# test-board-64.net
KiCad netlist of a schematic drawn in EAGLE
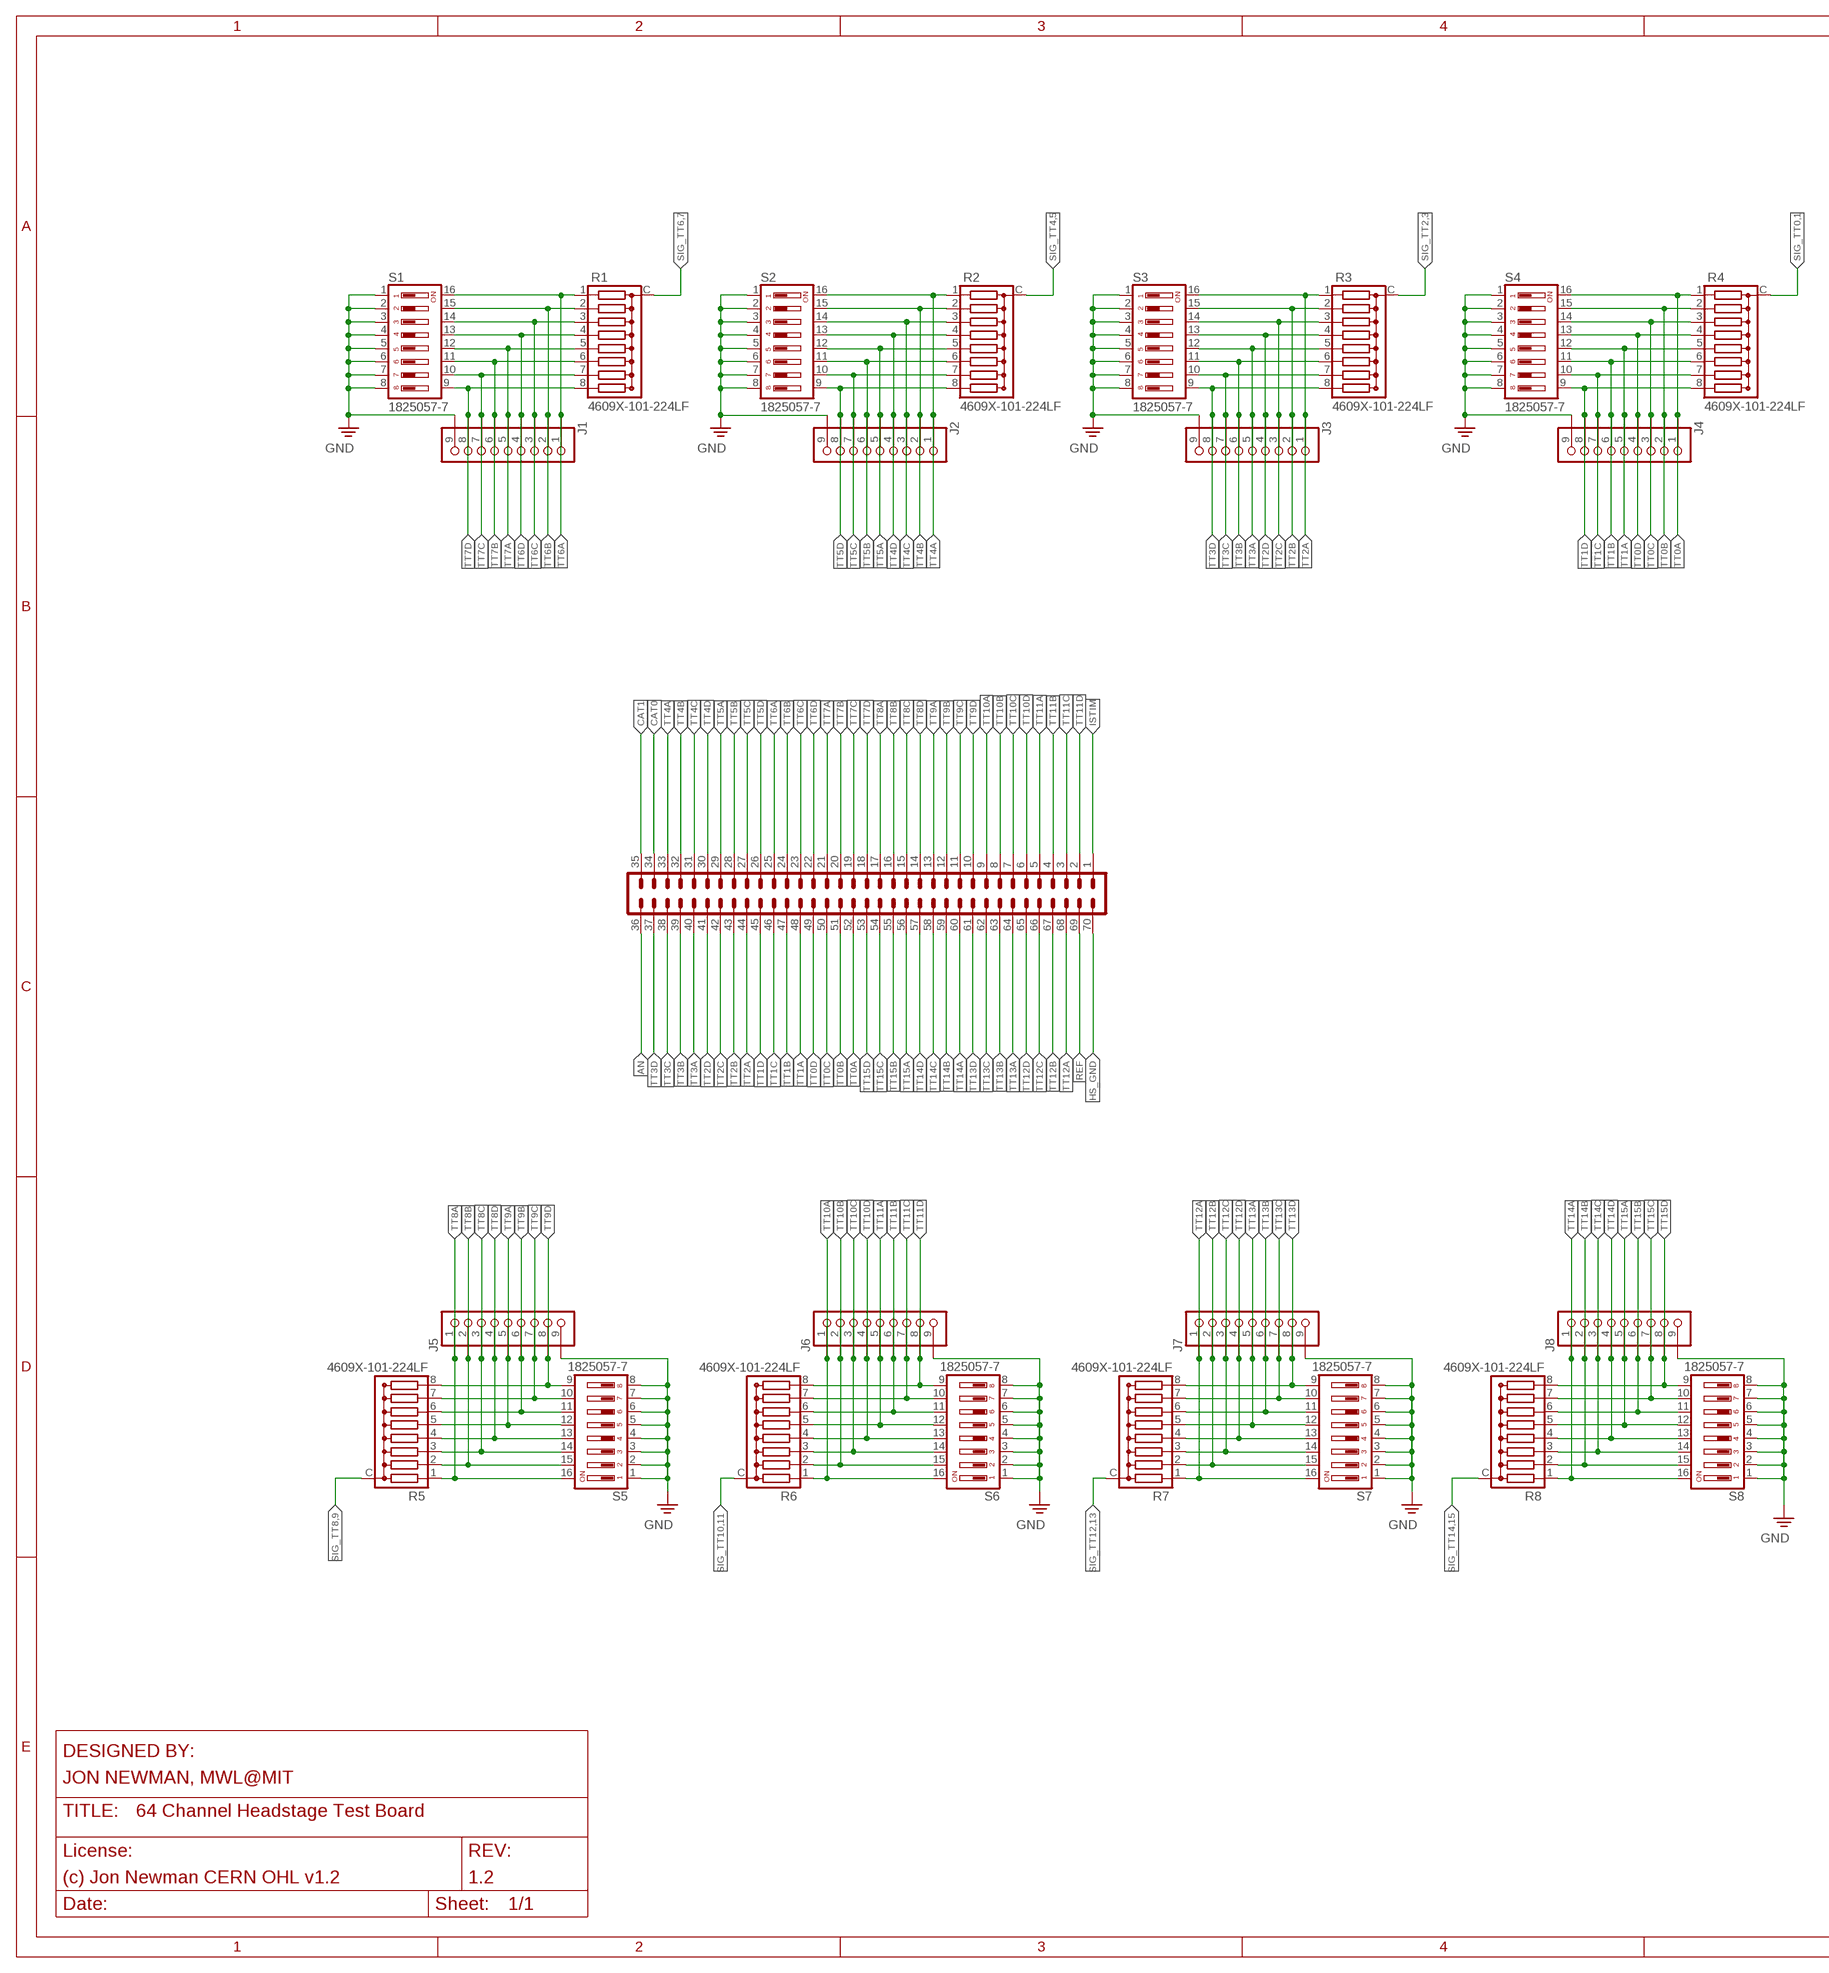
[diagram p0: schematic, sheet 1, part 1 of 2]
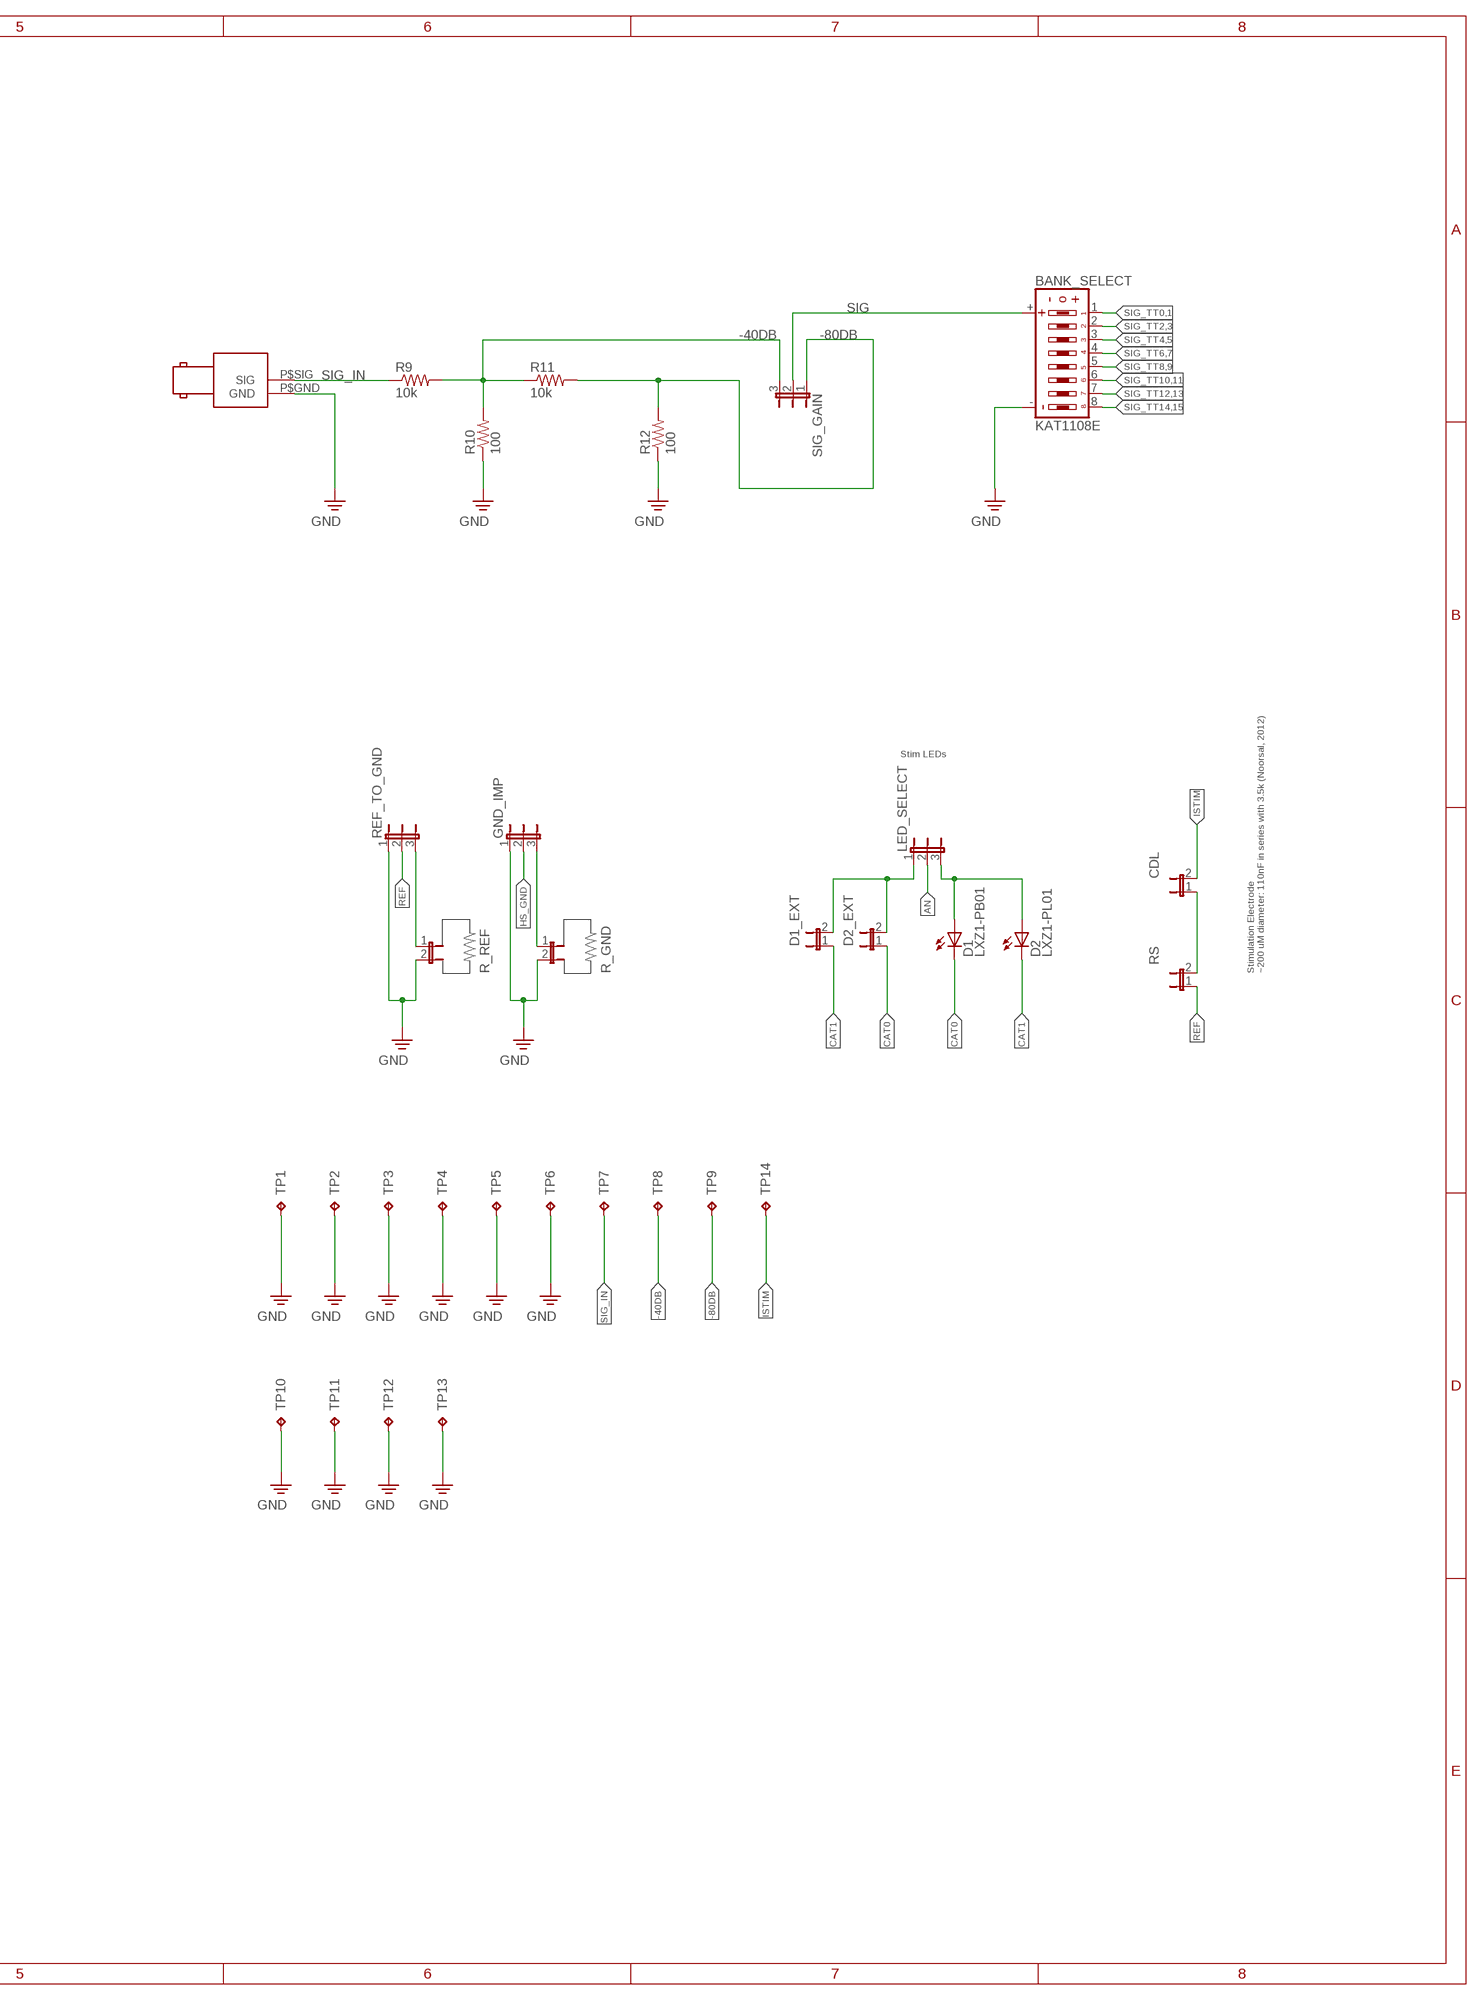
[diagram p1: schematic, sheet 1, part 2 of 2]

(export (version "E")
  (design (tool "Eeschema 10.0.6"))
  (components
    (comp (ref "BANK_SELECT")
      (value "KAT1108E")
      (footprint "eagle-import:206-124_DIP8-SPDT")
      (libsource (lib "eagle-import") (part "DIPSW-008-SPDT_206-124"))
    )
    (comp (ref "CDL")
      (value "SOC2-0.1\"")
      (footprint "eagle-import:JP2")
      (libsource (lib "eagle-import") (part "JP2E_THRU-HOLE"))
    )
    (comp (ref "D1")
      (value "LXZ1-PB01")
      (footprint "eagle-import:LXZ1")
      (libsource (lib "eagle-import") (part "LED_LXZ1"))
    )
    (comp (ref "D1_EXT")
      (value "SOC2-0.1\"")
      (footprint "eagle-import:JP2")
      (libsource (lib "eagle-import") (part "JP2E_THRU-HOLE"))
    )
    (comp (ref "D2")
      (value "LXZ1-PL01")
      (footprint "eagle-import:LXZ1")
      (libsource (lib "eagle-import") (part "LED_LXZ1"))
    )
    (comp (ref "D2_EXT")
      (value "SOC2-0.1\"")
      (footprint "eagle-import:JP2")
      (libsource (lib "eagle-import") (part "JP2E_THRU-HOLE"))
    )
    (comp (ref "GND_IMP")
      (value "JP3-0.1\"")
      (footprint "eagle-import:JP3")
      (libsource (lib "eagle-import") (part "JP3E"))
    )
    (comp (ref "HEADSTAGE")
      (value "DF40C-70DP-0.4V(51)")
      (footprint "eagle-import:DDF40-70REC-LRG")
      (libsource (lib "eagle-import") (part "PINHD-2X35_DF40REF-LRG"))
    )
    (comp (ref "J1")
      (value "PINHD-1X9")
      (footprint "eagle-import:1X09")
      (libsource (lib "eagle-import") (part "PINHD-1X9"))
    )
    (comp (ref "J2")
      (value "PINHD-1X9")
      (footprint "eagle-import:1X09")
      (libsource (lib "eagle-import") (part "PINHD-1X9"))
    )
    (comp (ref "J3")
      (value "PINHD-1X9")
      (footprint "eagle-import:1X09")
      (libsource (lib "eagle-import") (part "PINHD-1X9"))
    )
    (comp (ref "J4")
      (value "PINHD-1X9")
      (footprint "eagle-import:1X09")
      (libsource (lib "eagle-import") (part "PINHD-1X9"))
    )
    (comp (ref "J5")
      (value "PINHD-1X9")
      (footprint "eagle-import:1X09")
      (libsource (lib "eagle-import") (part "PINHD-1X9"))
    )
    (comp (ref "J6")
      (value "PINHD-1X9")
      (footprint "eagle-import:1X09")
      (libsource (lib "eagle-import") (part "PINHD-1X9"))
    )
    (comp (ref "J7")
      (value "PINHD-1X9")
      (footprint "eagle-import:1X09")
      (libsource (lib "eagle-import") (part "PINHD-1X9"))
    )
    (comp (ref "J8")
      (value "PINHD-1X9")
      (footprint "eagle-import:1X09")
      (libsource (lib "eagle-import") (part "PINHD-1X9"))
    )
    (comp (ref "LED_SELECT")
      (value "JP3-0.1\"")
      (footprint "eagle-import:JP3")
      (libsource (lib "eagle-import") (part "JP3E"))
    )
    (comp (ref "R1")
      (value "4609X-101-224LF")
      (footprint "eagle-import:RNX8-0.1")
      (libsource (lib "eagle-import") (part "RN1X8"))
    )
    (comp (ref "R2")
      (value "4609X-101-224LF")
      (footprint "eagle-import:RNX8-0.1")
      (libsource (lib "eagle-import") (part "RN1X8"))
    )
    (comp (ref "R3")
      (value "4609X-101-224LF")
      (footprint "eagle-import:RNX8-0.1")
      (libsource (lib "eagle-import") (part "RN1X8"))
    )
    (comp (ref "R4")
      (value "4609X-101-224LF")
      (footprint "eagle-import:RNX8-0.1")
      (libsource (lib "eagle-import") (part "RN1X8"))
    )
    (comp (ref "R5")
      (value "4609X-101-224LF")
      (footprint "eagle-import:RNX8-0.1")
      (libsource (lib "eagle-import") (part "RN1X8"))
    )
    (comp (ref "R6")
      (value "4609X-101-224LF")
      (footprint "eagle-import:RNX8-0.1")
      (libsource (lib "eagle-import") (part "RN1X8"))
    )
    (comp (ref "R7")
      (value "4609X-101-224LF")
      (footprint "eagle-import:RNX8-0.1")
      (libsource (lib "eagle-import") (part "RN1X8"))
    )
    (comp (ref "R8")
      (value "4609X-101-224LF")
      (footprint "eagle-import:RNX8-0.1")
      (libsource (lib "eagle-import") (part "RN1X8"))
    )
    (comp (ref "R9")
      (value "10k")
      (footprint "eagle-import:0805")
      (libsource (lib "eagle-import") (part "R_0805"))
    )
    (comp (ref "R10")
      (value "100")
      (footprint "eagle-import:0805")
      (libsource (lib "eagle-import") (part "R_0805"))
    )
    (comp (ref "R11")
      (value "10k")
      (footprint "eagle-import:0805")
      (libsource (lib "eagle-import") (part "R_0805"))
    )
    (comp (ref "R12")
      (value "100")
      (footprint "eagle-import:0805")
      (libsource (lib "eagle-import") (part "R_0805"))
    )
    (comp (ref "REF_TO_GND")
      (value "JP3-0.1\"")
      (footprint "eagle-import:JP3")
      (libsource (lib "eagle-import") (part "JP3E"))
    )
    (comp (ref "RS")
      (value "SOC2-0.1\"")
      (footprint "eagle-import:JP2")
      (libsource (lib "eagle-import") (part "JP2E_THRU-HOLE"))
    )
    (comp (ref "R_GND")
      (value "SOC2-0.1\"")
      (footprint "eagle-import:JP2")
      (libsource (lib "eagle-import") (part "JP2E_THRU-HOLE"))
    )
    (comp (ref "R_REF")
      (value "SOC2-0.1\"")
      (footprint "eagle-import:JP2")
      (libsource (lib "eagle-import") (part "JP2E_THRU-HOLE"))
    )
    (comp (ref "S1")
      (value "1825057-7")
      (footprint "eagle-import:ADE_DIP8-SPST")
      (libsource (lib "eagle-import") (part "DIPSW-008_ADE"))
    )
    (comp (ref "S2")
      (value "1825057-7")
      (footprint "eagle-import:ADE_DIP8-SPST")
      (libsource (lib "eagle-import") (part "DIPSW-008_ADE"))
    )
    (comp (ref "S3")
      (value "1825057-7")
      (footprint "eagle-import:ADE_DIP8-SPST")
      (libsource (lib "eagle-import") (part "DIPSW-008_ADE"))
    )
    (comp (ref "S4")
      (value "1825057-7")
      (footprint "eagle-import:ADE_DIP8-SPST")
      (libsource (lib "eagle-import") (part "DIPSW-008_ADE"))
    )
    (comp (ref "S5")
      (value "1825057-7")
      (footprint "eagle-import:ADE_DIP8-SPST")
      (libsource (lib "eagle-import") (part "DIPSW-008_ADE"))
    )
    (comp (ref "S6")
      (value "1825057-7")
      (footprint "eagle-import:ADE_DIP8-SPST")
      (libsource (lib "eagle-import") (part "DIPSW-008_ADE"))
    )
    (comp (ref "S7")
      (value "1825057-7")
      (footprint "eagle-import:ADE_DIP8-SPST")
      (libsource (lib "eagle-import") (part "DIPSW-008_ADE"))
    )
    (comp (ref "S8")
      (value "1825057-7")
      (footprint "eagle-import:ADE_DIP8-SPST")
      (libsource (lib "eagle-import") (part "DIPSW-008_ADE"))
    )
    (comp (ref "SIG_GAIN")
      (value "JP3-0.1\"")
      (footprint "eagle-import:JP3")
      (libsource (lib "eagle-import") (part "JP3E"))
    )
    (comp (ref "SIG_IN")
      (value "1-1634622-0")
      (footprint "eagle-import:BNC_RIGHT_ANGLE")
      (libsource (lib "eagle-import") (part "BNC_RIGHT_ANGLE"))
    )
    (comp (ref "TP1")
      (value "GND")
      (footprint "eagle-import:P1-20")
      (libsource (lib "eagle-import") (part "TPPAD1-20"))
    )
    (comp (ref "TP2")
      (value "GND")
      (footprint "eagle-import:P1-20")
      (libsource (lib "eagle-import") (part "TPPAD1-20"))
    )
    (comp (ref "TP3")
      (value "GND")
      (footprint "eagle-import:P1-20")
      (libsource (lib "eagle-import") (part "TPPAD1-20"))
    )
    (comp (ref "TP4")
      (value "GND")
      (footprint "eagle-import:P1-20")
      (libsource (lib "eagle-import") (part "TPPAD1-20"))
    )
    (comp (ref "TP5")
      (value "GND")
      (footprint "eagle-import:P1-20")
      (libsource (lib "eagle-import") (part "TPPAD1-20"))
    )
    (comp (ref "TP6")
      (value "GND")
      (footprint "eagle-import:P1-20")
      (libsource (lib "eagle-import") (part "TPPAD1-20"))
    )
    (comp (ref "TP7")
      (value "SIG_IN")
      (footprint "eagle-import:P1-20")
      (libsource (lib "eagle-import") (part "TPPAD1-20"))
    )
    (comp (ref "TP8")
      (value "-40dB")
      (footprint "eagle-import:P1-20")
      (libsource (lib "eagle-import") (part "TPPAD1-20"))
    )
    (comp (ref "TP9")
      (value "-80dB")
      (footprint "eagle-import:P1-20")
      (libsource (lib "eagle-import") (part "TPPAD1-20"))
    )
    (comp (ref "TP10")
      (value "TP_4-40")
      (footprint "eagle-import:4-40_PLATED")
      (libsource (lib "eagle-import") (part "TP_4-40"))
    )
    (comp (ref "TP11")
      (value "TP_4-40")
      (footprint "eagle-import:4-40_PLATED")
      (libsource (lib "eagle-import") (part "TP_4-40"))
    )
    (comp (ref "TP12")
      (value "TP_4-40")
      (footprint "eagle-import:4-40_PLATED")
      (libsource (lib "eagle-import") (part "TP_4-40"))
    )
    (comp (ref "TP13")
      (value "TP_4-40")
      (footprint "eagle-import:4-40_PLATED")
      (libsource (lib "eagle-import") (part "TP_4-40"))
    )
    (comp (ref "TP14")
      (value "V_ESTIM")
      (footprint "eagle-import:P1-20")
      (libsource (lib "eagle-import") (part "TPPAD1-20"))
    )
  )
  (nets
    (net (code "1") (name "-40DB") (class "Default")
      (node (ref "R10") (pin "2") (pinfunction "2_2") (pintype "passive"))
      (node (ref "R11") (pin "1") (pinfunction "1_1") (pintype "passive"))
      (node (ref "R9") (pin "2") (pinfunction "2_2") (pintype "passive"))
      (node (ref "SIG_GAIN") (pin "3") (pinfunction "3_3") (pintype "passive"))
      (node (ref "TP8") (pin "TP") (pinfunction "TP_TP") (pintype "input"))
    )
    (net (code "2") (name "-80DB") (class "Default")
      (node (ref "R11") (pin "2") (pinfunction "2_2") (pintype "passive"))
      (node (ref "R12") (pin "2") (pinfunction "2_2") (pintype "passive"))
      (node (ref "SIG_GAIN") (pin "1") (pinfunction "1_1") (pintype "passive"))
      (node (ref "TP9") (pin "TP") (pinfunction "TP_TP") (pintype "input"))
    )
    (net (code "3") (name "/SIG") (class "Default")
      (node (ref "BANK_SELECT") (pin "+") (pinfunction "+_+") (pintype "passive"))
      (node (ref "SIG_GAIN") (pin "2") (pinfunction "2_2") (pintype "passive"))
    )
    (net (code "4") (name "AN") (class "Default")
      (node (ref "HEADSTAGE") (pin "36") (pinfunction "36_36") (pintype "bidirectional"))
      (node (ref "LED_SELECT") (pin "2") (pinfunction "2_2") (pintype "passive"))
    )
    (net (code "5") (name "CAT0") (class "Default")
      (node (ref "D1") (pin "C") (pinfunction "C_C") (pintype "passive"))
      (node (ref "D2_EXT") (pin "1") (pinfunction "1_1") (pintype "passive"))
      (node (ref "HEADSTAGE") (pin "34") (pinfunction "34_34") (pintype "bidirectional"))
    )
    (net (code "6") (name "CAT1") (class "Default")
      (node (ref "D1_EXT") (pin "1") (pinfunction "1_1") (pintype "passive"))
      (node (ref "D2") (pin "C") (pinfunction "C_C") (pintype "passive"))
      (node (ref "HEADSTAGE") (pin "35") (pinfunction "35_35") (pintype "bidirectional"))
    )
    (net (code "7") (name "GND") (class "Default")
      (node (ref "BANK_SELECT") (pin "-") (pinfunction "-_-") (pintype "passive"))
      (node (ref "GND_IMP") (pin "1") (pinfunction "1_1") (pintype "passive"))
      (node (ref "J1") (pin "9") (pinfunction "9_9") (pintype "passive"))
      (node (ref "J2") (pin "9") (pinfunction "9_9") (pintype "passive"))
      (node (ref "J3") (pin "9") (pinfunction "9_9") (pintype "passive"))
      (node (ref "J4") (pin "9") (pinfunction "9_9") (pintype "passive"))
      (node (ref "J5") (pin "9") (pinfunction "9_9") (pintype "passive"))
      (node (ref "J6") (pin "9") (pinfunction "9_9") (pintype "passive"))
      (node (ref "J7") (pin "9") (pinfunction "9_9") (pintype "passive"))
      (node (ref "J8") (pin "9") (pinfunction "9_9") (pintype "passive"))
      (node (ref "R10") (pin "1") (pinfunction "1_1") (pintype "passive"))
      (node (ref "R12") (pin "1") (pinfunction "1_1") (pintype "passive"))
      (node (ref "REF_TO_GND") (pin "1") (pinfunction "1_1") (pintype "passive"))
      (node (ref "R_GND") (pin "2") (pinfunction "2_2") (pintype "passive"))
      (node (ref "R_REF") (pin "2") (pinfunction "2_2") (pintype "passive"))
      (node (ref "S1") (pin "1") (pinfunction "1_1") (pintype "passive"))
      (node (ref "S1") (pin "2") (pinfunction "2_2") (pintype "passive"))
      (node (ref "S1") (pin "3") (pinfunction "3_3") (pintype "passive"))
      (node (ref "S1") (pin "4") (pinfunction "4_4") (pintype "passive"))
      (node (ref "S1") (pin "5") (pinfunction "5_5") (pintype "passive"))
      (node (ref "S1") (pin "6") (pinfunction "6_6") (pintype "passive"))
      (node (ref "S1") (pin "7") (pinfunction "7_7") (pintype "passive"))
      (node (ref "S1") (pin "8") (pinfunction "8_8") (pintype "passive"))
      (node (ref "S2") (pin "1") (pinfunction "1_1") (pintype "passive"))
      (node (ref "S2") (pin "2") (pinfunction "2_2") (pintype "passive"))
      (node (ref "S2") (pin "3") (pinfunction "3_3") (pintype "passive"))
      (node (ref "S2") (pin "4") (pinfunction "4_4") (pintype "passive"))
      (node (ref "S2") (pin "5") (pinfunction "5_5") (pintype "passive"))
      (node (ref "S2") (pin "6") (pinfunction "6_6") (pintype "passive"))
      (node (ref "S2") (pin "7") (pinfunction "7_7") (pintype "passive"))
      (node (ref "S2") (pin "8") (pinfunction "8_8") (pintype "passive"))
      (node (ref "S3") (pin "1") (pinfunction "1_1") (pintype "passive"))
      (node (ref "S3") (pin "2") (pinfunction "2_2") (pintype "passive"))
      (node (ref "S3") (pin "3") (pinfunction "3_3") (pintype "passive"))
      (node (ref "S3") (pin "4") (pinfunction "4_4") (pintype "passive"))
      (node (ref "S3") (pin "5") (pinfunction "5_5") (pintype "passive"))
      (node (ref "S3") (pin "6") (pinfunction "6_6") (pintype "passive"))
      (node (ref "S3") (pin "7") (pinfunction "7_7") (pintype "passive"))
      (node (ref "S3") (pin "8") (pinfunction "8_8") (pintype "passive"))
      (node (ref "S4") (pin "1") (pinfunction "1_1") (pintype "passive"))
      (node (ref "S4") (pin "2") (pinfunction "2_2") (pintype "passive"))
      (node (ref "S4") (pin "3") (pinfunction "3_3") (pintype "passive"))
      (node (ref "S4") (pin "4") (pinfunction "4_4") (pintype "passive"))
      (node (ref "S4") (pin "5") (pinfunction "5_5") (pintype "passive"))
      (node (ref "S4") (pin "6") (pinfunction "6_6") (pintype "passive"))
      (node (ref "S4") (pin "7") (pinfunction "7_7") (pintype "passive"))
      (node (ref "S4") (pin "8") (pinfunction "8_8") (pintype "passive"))
      (node (ref "S5") (pin "1") (pinfunction "1_1") (pintype "passive"))
      (node (ref "S5") (pin "2") (pinfunction "2_2") (pintype "passive"))
      (node (ref "S5") (pin "3") (pinfunction "3_3") (pintype "passive"))
      (node (ref "S5") (pin "4") (pinfunction "4_4") (pintype "passive"))
      (node (ref "S5") (pin "5") (pinfunction "5_5") (pintype "passive"))
      (node (ref "S5") (pin "6") (pinfunction "6_6") (pintype "passive"))
      (node (ref "S5") (pin "7") (pinfunction "7_7") (pintype "passive"))
      (node (ref "S5") (pin "8") (pinfunction "8_8") (pintype "passive"))
      (node (ref "S6") (pin "1") (pinfunction "1_1") (pintype "passive"))
      (node (ref "S6") (pin "2") (pinfunction "2_2") (pintype "passive"))
      (node (ref "S6") (pin "3") (pinfunction "3_3") (pintype "passive"))
      (node (ref "S6") (pin "4") (pinfunction "4_4") (pintype "passive"))
      (node (ref "S6") (pin "5") (pinfunction "5_5") (pintype "passive"))
      (node (ref "S6") (pin "6") (pinfunction "6_6") (pintype "passive"))
      (node (ref "S6") (pin "7") (pinfunction "7_7") (pintype "passive"))
      (node (ref "S6") (pin "8") (pinfunction "8_8") (pintype "passive"))
      (node (ref "S7") (pin "1") (pinfunction "1_1") (pintype "passive"))
      (node (ref "S7") (pin "2") (pinfunction "2_2") (pintype "passive"))
      (node (ref "S7") (pin "3") (pinfunction "3_3") (pintype "passive"))
      (node (ref "S7") (pin "4") (pinfunction "4_4") (pintype "passive"))
      (node (ref "S7") (pin "5") (pinfunction "5_5") (pintype "passive"))
      (node (ref "S7") (pin "6") (pinfunction "6_6") (pintype "passive"))
      (node (ref "S7") (pin "7") (pinfunction "7_7") (pintype "passive"))
      (node (ref "S7") (pin "8") (pinfunction "8_8") (pintype "passive"))
      (node (ref "S8") (pin "1") (pinfunction "1_1") (pintype "passive"))
      (node (ref "S8") (pin "2") (pinfunction "2_2") (pintype "passive"))
      (node (ref "S8") (pin "3") (pinfunction "3_3") (pintype "passive"))
      (node (ref "S8") (pin "4") (pinfunction "4_4") (pintype "passive"))
      (node (ref "S8") (pin "5") (pinfunction "5_5") (pintype "passive"))
      (node (ref "S8") (pin "6") (pinfunction "6_6") (pintype "passive"))
      (node (ref "S8") (pin "7") (pinfunction "7_7") (pintype "passive"))
      (node (ref "S8") (pin "8") (pinfunction "8_8") (pintype "passive"))
      (node (ref "SIG_IN") (pin "P$GND") (pinfunction "GND_P$GND") (pintype "bidirectional"))
      (node (ref "TP1") (pin "TP") (pinfunction "TP_TP") (pintype "input"))
      (node (ref "TP10") (pin "P$1") (pinfunction "TP_P$1") (pintype "input"))
      (node (ref "TP11") (pin "P$1") (pinfunction "TP_P$1") (pintype "input"))
      (node (ref "TP12") (pin "P$1") (pinfunction "TP_P$1") (pintype "input"))
      (node (ref "TP13") (pin "P$1") (pinfunction "TP_P$1") (pintype "input"))
      (node (ref "TP2") (pin "TP") (pinfunction "TP_TP") (pintype "input"))
      (node (ref "TP3") (pin "TP") (pinfunction "TP_TP") (pintype "input"))
      (node (ref "TP4") (pin "TP") (pinfunction "TP_TP") (pintype "input"))
      (node (ref "TP5") (pin "TP") (pinfunction "TP_TP") (pintype "input"))
      (node (ref "TP6") (pin "TP") (pinfunction "TP_TP") (pintype "input"))
    )
    (net (code "8") (name "HS_GND") (class "Default")
      (node (ref "GND_IMP") (pin "2") (pinfunction "2_2") (pintype "passive"))
      (node (ref "HEADSTAGE") (pin "70") (pinfunction "70_70") (pintype "bidirectional"))
    )
    (net (code "9") (name "ISTIM") (class "Default")
      (node (ref "CDL") (pin "2") (pinfunction "2_2") (pintype "passive"))
      (node (ref "HEADSTAGE") (pin "1") (pinfunction "1_1") (pintype "bidirectional"))
      (node (ref "TP14") (pin "TP") (pinfunction "TP_TP") (pintype "input"))
    )
    (net (code "10") (name "Net-(CDL-Pad1)") (class "Default")
      (node (ref "CDL") (pin "1") (pinfunction "1_1") (pintype "passive"))
      (node (ref "RS") (pin "2") (pinfunction "2_2") (pintype "passive"))
    )
    (net (code "11") (name "Net-(D1-PadA)") (class "Default")
      (node (ref "D1") (pin "A") (pinfunction "A_A") (pintype "passive"))
      (node (ref "D2") (pin "A") (pinfunction "A_A") (pintype "passive"))
      (node (ref "LED_SELECT") (pin "3") (pinfunction "3_3") (pintype "passive"))
    )
    (net (code "12") (name "Net-(D1_EXT-Pad2)") (class "Default")
      (node (ref "D1_EXT") (pin "2") (pinfunction "2_2") (pintype "passive"))
      (node (ref "D2_EXT") (pin "2") (pinfunction "2_2") (pintype "passive"))
      (node (ref "LED_SELECT") (pin "1") (pinfunction "1_1") (pintype "passive"))
    )
    (net (code "13") (name "Net-(GND_IMP-Pad3)") (class "Default")
      (node (ref "GND_IMP") (pin "3") (pinfunction "3_3") (pintype "passive"))
      (node (ref "R_GND") (pin "1") (pinfunction "1_1") (pintype "passive"))
    )
    (net (code "14") (name "Net-(REF_TO_GND-Pad3)") (class "Default")
      (node (ref "REF_TO_GND") (pin "3") (pinfunction "3_3") (pintype "passive"))
      (node (ref "R_REF") (pin "1") (pinfunction "1_1") (pintype "passive"))
    )
    (net (code "15") (name "REF") (class "Default")
      (node (ref "HEADSTAGE") (pin "69") (pinfunction "69_69") (pintype "bidirectional"))
      (node (ref "REF_TO_GND") (pin "2") (pinfunction "2_2") (pintype "passive"))
      (node (ref "RS") (pin "1") (pinfunction "1_1") (pintype "passive"))
    )
    (net (code "16") (name "SIG_IN") (class "Default")
      (node (ref "R9") (pin "1") (pinfunction "1_1") (pintype "passive"))
      (node (ref "SIG_IN") (pin "P$SIG") (pinfunction "SIG_P$SIG") (pintype "bidirectional"))
      (node (ref "TP7") (pin "TP") (pinfunction "TP_TP") (pintype "input"))
    )
    (net (code "17") (name "SIG_TT0,1") (class "Default")
      (node (ref "BANK_SELECT") (pin "1") (pinfunction "1_1") (pintype "passive"))
      (node (ref "R4") (pin "C") (pinfunction "C_C") (pintype "passive"))
    )
    (net (code "18") (name "SIG_TT2,3") (class "Default")
      (node (ref "BANK_SELECT") (pin "2") (pinfunction "2_2") (pintype "passive"))
      (node (ref "R3") (pin "C") (pinfunction "C_C") (pintype "passive"))
    )
    (net (code "19") (name "SIG_TT4,5") (class "Default")
      (node (ref "BANK_SELECT") (pin "3") (pinfunction "3_3") (pintype "passive"))
      (node (ref "R2") (pin "C") (pinfunction "C_C") (pintype "passive"))
    )
    (net (code "20") (name "SIG_TT6,7") (class "Default")
      (node (ref "BANK_SELECT") (pin "4") (pinfunction "4_4") (pintype "passive"))
      (node (ref "R1") (pin "C") (pinfunction "C_C") (pintype "passive"))
    )
    (net (code "21") (name "SIG_TT8,9") (class "Default")
      (node (ref "BANK_SELECT") (pin "5") (pinfunction "5_5") (pintype "passive"))
      (node (ref "R5") (pin "C") (pinfunction "C_C") (pintype "passive"))
    )
    (net (code "22") (name "SIG_TT10,11") (class "Default")
      (node (ref "BANK_SELECT") (pin "6") (pinfunction "6_6") (pintype "passive"))
      (node (ref "R6") (pin "C") (pinfunction "C_C") (pintype "passive"))
    )
    (net (code "23") (name "SIG_TT12,13") (class "Default")
      (node (ref "BANK_SELECT") (pin "7") (pinfunction "7_7") (pintype "passive"))
      (node (ref "R7") (pin "C") (pinfunction "C_C") (pintype "passive"))
    )
    (net (code "24") (name "SIG_TT14,15") (class "Default")
      (node (ref "BANK_SELECT") (pin "8") (pinfunction "8_8") (pintype "passive"))
      (node (ref "R8") (pin "C") (pinfunction "C_C") (pintype "passive"))
    )
    (net (code "25") (name "TT0A") (class "Default")
      (node (ref "HEADSTAGE") (pin "52") (pinfunction "52_52") (pintype "bidirectional"))
      (node (ref "J4") (pin "1") (pinfunction "1_1") (pintype "passive"))
      (node (ref "R4") (pin "1") (pinfunction "1_1") (pintype "passive"))
      (node (ref "S4") (pin "16") (pinfunction "16_16") (pintype "passive"))
    )
    (net (code "26") (name "TT0B") (class "Default")
      (node (ref "HEADSTAGE") (pin "51") (pinfunction "51_51") (pintype "bidirectional"))
      (node (ref "J4") (pin "2") (pinfunction "2_2") (pintype "passive"))
      (node (ref "R4") (pin "2") (pinfunction "2_2") (pintype "passive"))
      (node (ref "S4") (pin "15") (pinfunction "15_15") (pintype "passive"))
    )
    (net (code "27") (name "TT0C") (class "Default")
      (node (ref "HEADSTAGE") (pin "50") (pinfunction "50_50") (pintype "bidirectional"))
      (node (ref "J4") (pin "3") (pinfunction "3_3") (pintype "passive"))
      (node (ref "R4") (pin "3") (pinfunction "3_3") (pintype "passive"))
      (node (ref "S4") (pin "14") (pinfunction "14_14") (pintype "passive"))
    )
    (net (code "28") (name "TT0D") (class "Default")
      (node (ref "HEADSTAGE") (pin "49") (pinfunction "49_49") (pintype "bidirectional"))
      (node (ref "J4") (pin "4") (pinfunction "4_4") (pintype "passive"))
      (node (ref "R4") (pin "4") (pinfunction "4_4") (pintype "passive"))
      (node (ref "S4") (pin "13") (pinfunction "13_13") (pintype "passive"))
    )
    (net (code "29") (name "TT1A") (class "Default")
      (node (ref "HEADSTAGE") (pin "48") (pinfunction "48_48") (pintype "bidirectional"))
      (node (ref "J4") (pin "5") (pinfunction "5_5") (pintype "passive"))
      (node (ref "R4") (pin "5") (pinfunction "5_5") (pintype "passive"))
      (node (ref "S4") (pin "12") (pinfunction "12_12") (pintype "passive"))
    )
    (net (code "30") (name "TT1B") (class "Default")
      (node (ref "HEADSTAGE") (pin "47") (pinfunction "47_47") (pintype "bidirectional"))
      (node (ref "J4") (pin "6") (pinfunction "6_6") (pintype "passive"))
      (node (ref "R4") (pin "6") (pinfunction "6_6") (pintype "passive"))
      (node (ref "S4") (pin "11") (pinfunction "11_11") (pintype "passive"))
    )
    (net (code "31") (name "TT1C") (class "Default")
      (node (ref "HEADSTAGE") (pin "46") (pinfunction "46_46") (pintype "bidirectional"))
      (node (ref "J4") (pin "7") (pinfunction "7_7") (pintype "passive"))
      (node (ref "R4") (pin "7") (pinfunction "7_7") (pintype "passive"))
      (node (ref "S4") (pin "10") (pinfunction "10_10") (pintype "passive"))
    )
    (net (code "32") (name "TT1D") (class "Default")
      (node (ref "HEADSTAGE") (pin "45") (pinfunction "45_45") (pintype "bidirectional"))
      (node (ref "J4") (pin "8") (pinfunction "8_8") (pintype "passive"))
      (node (ref "R4") (pin "8") (pinfunction "8_8") (pintype "passive"))
      (node (ref "S4") (pin "9") (pinfunction "9_9") (pintype "passive"))
    )
    (net (code "33") (name "TT2A") (class "Default")
      (node (ref "HEADSTAGE") (pin "44") (pinfunction "44_44") (pintype "bidirectional"))
      (node (ref "J3") (pin "1") (pinfunction "1_1") (pintype "passive"))
      (node (ref "R3") (pin "1") (pinfunction "1_1") (pintype "passive"))
      (node (ref "S3") (pin "16") (pinfunction "16_16") (pintype "passive"))
    )
    (net (code "34") (name "TT2B") (class "Default")
      (node (ref "HEADSTAGE") (pin "43") (pinfunction "43_43") (pintype "bidirectional"))
      (node (ref "J3") (pin "2") (pinfunction "2_2") (pintype "passive"))
      (node (ref "R3") (pin "2") (pinfunction "2_2") (pintype "passive"))
      (node (ref "S3") (pin "15") (pinfunction "15_15") (pintype "passive"))
    )
    (net (code "35") (name "TT2C") (class "Default")
      (node (ref "HEADSTAGE") (pin "42") (pinfunction "42_42") (pintype "bidirectional"))
      (node (ref "J3") (pin "3") (pinfunction "3_3") (pintype "passive"))
      (node (ref "R3") (pin "3") (pinfunction "3_3") (pintype "passive"))
      (node (ref "S3") (pin "14") (pinfunction "14_14") (pintype "passive"))
    )
    (net (code "36") (name "TT2D") (class "Default")
      (node (ref "HEADSTAGE") (pin "41") (pinfunction "41_41") (pintype "bidirectional"))
      (node (ref "J3") (pin "4") (pinfunction "4_4") (pintype "passive"))
      (node (ref "R3") (pin "4") (pinfunction "4_4") (pintype "passive"))
      (node (ref "S3") (pin "13") (pinfunction "13_13") (pintype "passive"))
    )
    (net (code "37") (name "TT3A") (class "Default")
      (node (ref "HEADSTAGE") (pin "40") (pinfunction "40_40") (pintype "bidirectional"))
      (node (ref "J3") (pin "5") (pinfunction "5_5") (pintype "passive"))
      (node (ref "R3") (pin "5") (pinfunction "5_5") (pintype "passive"))
      (node (ref "S3") (pin "12") (pinfunction "12_12") (pintype "passive"))
    )
    (net (code "38") (name "TT3B") (class "Default")
      (node (ref "HEADSTAGE") (pin "39") (pinfunction "39_39") (pintype "bidirectional"))
      (node (ref "J3") (pin "6") (pinfunction "6_6") (pintype "passive"))
      (node (ref "R3") (pin "6") (pinfunction "6_6") (pintype "passive"))
      (node (ref "S3") (pin "11") (pinfunction "11_11") (pintype "passive"))
    )
    (net (code "39") (name "TT3C") (class "Default")
      (node (ref "HEADSTAGE") (pin "38") (pinfunction "38_38") (pintype "bidirectional"))
      (node (ref "J3") (pin "7") (pinfunction "7_7") (pintype "passive"))
      (node (ref "R3") (pin "7") (pinfunction "7_7") (pintype "passive"))
      (node (ref "S3") (pin "10") (pinfunction "10_10") (pintype "passive"))
    )
    (net (code "40") (name "TT3D") (class "Default")
      (node (ref "HEADSTAGE") (pin "37") (pinfunction "37_37") (pintype "bidirectional"))
      (node (ref "J3") (pin "8") (pinfunction "8_8") (pintype "passive"))
      (node (ref "R3") (pin "8") (pinfunction "8_8") (pintype "passive"))
      (node (ref "S3") (pin "9") (pinfunction "9_9") (pintype "passive"))
    )
    (net (code "41") (name "TT4A") (class "Default")
      (node (ref "HEADSTAGE") (pin "33") (pinfunction "33_33") (pintype "bidirectional"))
      (node (ref "J2") (pin "1") (pinfunction "1_1") (pintype "passive"))
      (node (ref "R2") (pin "1") (pinfunction "1_1") (pintype "passive"))
      (node (ref "S2") (pin "16") (pinfunction "16_16") (pintype "passive"))
    )
    (net (code "42") (name "TT4B") (class "Default")
      (node (ref "HEADSTAGE") (pin "32") (pinfunction "32_32") (pintype "bidirectional"))
      (node (ref "J2") (pin "2") (pinfunction "2_2") (pintype "passive"))
      (node (ref "R2") (pin "2") (pinfunction "2_2") (pintype "passive"))
      (node (ref "S2") (pin "15") (pinfunction "15_15") (pintype "passive"))
    )
    (net (code "43") (name "TT4C") (class "Default")
      (node (ref "HEADSTAGE") (pin "31") (pinfunction "31_31") (pintype "bidirectional"))
      (node (ref "J2") (pin "3") (pinfunction "3_3") (pintype "passive"))
      (node (ref "R2") (pin "3") (pinfunction "3_3") (pintype "passive"))
      (node (ref "S2") (pin "14") (pinfunction "14_14") (pintype "passive"))
    )
    (net (code "44") (name "TT4D") (class "Default")
      (node (ref "HEADSTAGE") (pin "30") (pinfunction "30_30") (pintype "bidirectional"))
      (node (ref "J2") (pin "4") (pinfunction "4_4") (pintype "passive"))
      (node (ref "R2") (pin "4") (pinfunction "4_4") (pintype "passive"))
      (node (ref "S2") (pin "13") (pinfunction "13_13") (pintype "passive"))
    )
    (net (code "45") (name "TT5A") (class "Default")
      (node (ref "HEADSTAGE") (pin "29") (pinfunction "29_29") (pintype "bidirectional"))
      (node (ref "J2") (pin "5") (pinfunction "5_5") (pintype "passive"))
      (node (ref "R2") (pin "5") (pinfunction "5_5") (pintype "passive"))
      (node (ref "S2") (pin "12") (pinfunction "12_12") (pintype "passive"))
    )
    (net (code "46") (name "TT5B") (class "Default")
      (node (ref "HEADSTAGE") (pin "28") (pinfunction "28_28") (pintype "bidirectional"))
      (node (ref "J2") (pin "6") (pinfunction "6_6") (pintype "passive"))
      (node (ref "R2") (pin "6") (pinfunction "6_6") (pintype "passive"))
      (node (ref "S2") (pin "11") (pinfunction "11_11") (pintype "passive"))
    )
    (net (code "47") (name "TT5C") (class "Default")
      (node (ref "HEADSTAGE") (pin "27") (pinfunction "27_27") (pintype "bidirectional"))
      (node (ref "J2") (pin "7") (pinfunction "7_7") (pintype "passive"))
      (node (ref "R2") (pin "7") (pinfunction "7_7") (pintype "passive"))
      (node (ref "S2") (pin "10") (pinfunction "10_10") (pintype "passive"))
    )
    (net (code "48") (name "TT5D") (class "Default")
      (node (ref "HEADSTAGE") (pin "26") (pinfunction "26_26") (pintype "bidirectional"))
      (node (ref "J2") (pin "8") (pinfunction "8_8") (pintype "passive"))
      (node (ref "R2") (pin "8") (pinfunction "8_8") (pintype "passive"))
      (node (ref "S2") (pin "9") (pinfunction "9_9") (pintype "passive"))
    )
    (net (code "49") (name "TT6A") (class "Default")
      (node (ref "HEADSTAGE") (pin "25") (pinfunction "25_25") (pintype "bidirectional"))
      (node (ref "J1") (pin "1") (pinfunction "1_1") (pintype "passive"))
      (node (ref "R1") (pin "1") (pinfunction "1_1") (pintype "passive"))
      (node (ref "S1") (pin "16") (pinfunction "16_16") (pintype "passive"))
    )
    (net (code "50") (name "TT6B") (class "Default")
      (node (ref "HEADSTAGE") (pin "24") (pinfunction "24_24") (pintype "bidirectional"))
      (node (ref "J1") (pin "2") (pinfunction "2_2") (pintype "passive"))
      (node (ref "R1") (pin "2") (pinfunction "2_2") (pintype "passive"))
      (node (ref "S1") (pin "15") (pinfunction "15_15") (pintype "passive"))
    )
    (net (code "51") (name "TT6C") (class "Default")
      (node (ref "HEADSTAGE") (pin "23") (pinfunction "23_23") (pintype "bidirectional"))
      (node (ref "J1") (pin "3") (pinfunction "3_3") (pintype "passive"))
      (node (ref "R1") (pin "3") (pinfunction "3_3") (pintype "passive"))
      (node (ref "S1") (pin "14") (pinfunction "14_14") (pintype "passive"))
    )
    (net (code "52") (name "TT6D") (class "Default")
      (node (ref "HEADSTAGE") (pin "22") (pinfunction "22_22") (pintype "bidirectional"))
      (node (ref "J1") (pin "4") (pinfunction "4_4") (pintype "passive"))
      (node (ref "R1") (pin "4") (pinfunction "4_4") (pintype "passive"))
      (node (ref "S1") (pin "13") (pinfunction "13_13") (pintype "passive"))
    )
    (net (code "53") (name "TT7A") (class "Default")
      (node (ref "HEADSTAGE") (pin "21") (pinfunction "21_21") (pintype "bidirectional"))
      (node (ref "J1") (pin "5") (pinfunction "5_5") (pintype "passive"))
      (node (ref "R1") (pin "5") (pinfunction "5_5") (pintype "passive"))
      (node (ref "S1") (pin "12") (pinfunction "12_12") (pintype "passive"))
    )
    (net (code "54") (name "TT7B") (class "Default")
      (node (ref "HEADSTAGE") (pin "20") (pinfunction "20_20") (pintype "bidirectional"))
      (node (ref "J1") (pin "6") (pinfunction "6_6") (pintype "passive"))
      (node (ref "R1") (pin "6") (pinfunction "6_6") (pintype "passive"))
      (node (ref "S1") (pin "11") (pinfunction "11_11") (pintype "passive"))
    )
    (net (code "55") (name "TT7C") (class "Default")
      (node (ref "HEADSTAGE") (pin "19") (pinfunction "19_19") (pintype "bidirectional"))
      (node (ref "J1") (pin "7") (pinfunction "7_7") (pintype "passive"))
      (node (ref "R1") (pin "7") (pinfunction "7_7") (pintype "passive"))
      (node (ref "S1") (pin "10") (pinfunction "10_10") (pintype "passive"))
    )
    (net (code "56") (name "TT7D") (class "Default")
      (node (ref "HEADSTAGE") (pin "18") (pinfunction "18_18") (pintype "bidirectional"))
      (node (ref "J1") (pin "8") (pinfunction "8_8") (pintype "passive"))
      (node (ref "R1") (pin "8") (pinfunction "8_8") (pintype "passive"))
      (node (ref "S1") (pin "9") (pinfunction "9_9") (pintype "passive"))
    )
    (net (code "57") (name "TT8A") (class "Default")
      (node (ref "HEADSTAGE") (pin "17") (pinfunction "17_17") (pintype "bidirectional"))
      (node (ref "J5") (pin "1") (pinfunction "1_1") (pintype "passive"))
      (node (ref "R5") (pin "1") (pinfunction "1_1") (pintype "passive"))
      (node (ref "S5") (pin "16") (pinfunction "16_16") (pintype "passive"))
    )
    (net (code "58") (name "TT8B") (class "Default")
      (node (ref "HEADSTAGE") (pin "16") (pinfunction "16_16") (pintype "bidirectional"))
      (node (ref "J5") (pin "2") (pinfunction "2_2") (pintype "passive"))
      (node (ref "R5") (pin "2") (pinfunction "2_2") (pintype "passive"))
      (node (ref "S5") (pin "15") (pinfunction "15_15") (pintype "passive"))
    )
    (net (code "59") (name "TT8C") (class "Default")
      (node (ref "HEADSTAGE") (pin "15") (pinfunction "15_15") (pintype "bidirectional"))
      (node (ref "J5") (pin "3") (pinfunction "3_3") (pintype "passive"))
      (node (ref "R5") (pin "3") (pinfunction "3_3") (pintype "passive"))
      (node (ref "S5") (pin "14") (pinfunction "14_14") (pintype "passive"))
    )
    (net (code "60") (name "TT8D") (class "Default")
      (node (ref "HEADSTAGE") (pin "14") (pinfunction "14_14") (pintype "bidirectional"))
      (node (ref "J5") (pin "4") (pinfunction "4_4") (pintype "passive"))
      (node (ref "R5") (pin "4") (pinfunction "4_4") (pintype "passive"))
      (node (ref "S5") (pin "13") (pinfunction "13_13") (pintype "passive"))
    )
    (net (code "61") (name "TT9A") (class "Default")
      (node (ref "HEADSTAGE") (pin "13") (pinfunction "13_13") (pintype "bidirectional"))
      (node (ref "J5") (pin "5") (pinfunction "5_5") (pintype "passive"))
      (node (ref "R5") (pin "5") (pinfunction "5_5") (pintype "passive"))
      (node (ref "S5") (pin "12") (pinfunction "12_12") (pintype "passive"))
    )
    (net (code "62") (name "TT9B") (class "Default")
      (node (ref "HEADSTAGE") (pin "12") (pinfunction "12_12") (pintype "bidirectional"))
      (node (ref "J5") (pin "6") (pinfunction "6_6") (pintype "passive"))
      (node (ref "R5") (pin "6") (pinfunction "6_6") (pintype "passive"))
      (node (ref "S5") (pin "11") (pinfunction "11_11") (pintype "passive"))
    )
    (net (code "63") (name "TT9C") (class "Default")
      (node (ref "HEADSTAGE") (pin "11") (pinfunction "11_11") (pintype "bidirectional"))
      (node (ref "J5") (pin "7") (pinfunction "7_7") (pintype "passive"))
      (node (ref "R5") (pin "7") (pinfunction "7_7") (pintype "passive"))
      (node (ref "S5") (pin "10") (pinfunction "10_10") (pintype "passive"))
    )
    (net (code "64") (name "TT9D") (class "Default")
      (node (ref "HEADSTAGE") (pin "10") (pinfunction "10_10") (pintype "bidirectional"))
      (node (ref "J5") (pin "8") (pinfunction "8_8") (pintype "passive"))
      (node (ref "R5") (pin "8") (pinfunction "8_8") (pintype "passive"))
      (node (ref "S5") (pin "9") (pinfunction "9_9") (pintype "passive"))
    )
    (net (code "65") (name "TT10A") (class "Default")
      (node (ref "HEADSTAGE") (pin "9") (pinfunction "9_9") (pintype "bidirectional"))
      (node (ref "J6") (pin "1") (pinfunction "1_1") (pintype "passive"))
      (node (ref "R6") (pin "1") (pinfunction "1_1") (pintype "passive"))
      (node (ref "S6") (pin "16") (pinfunction "16_16") (pintype "passive"))
    )
    (net (code "66") (name "TT10B") (class "Default")
      (node (ref "HEADSTAGE") (pin "8") (pinfunction "8_8") (pintype "bidirectional"))
      (node (ref "J6") (pin "2") (pinfunction "2_2") (pintype "passive"))
      (node (ref "R6") (pin "2") (pinfunction "2_2") (pintype "passive"))
      (node (ref "S6") (pin "15") (pinfunction "15_15") (pintype "passive"))
    )
    (net (code "67") (name "TT10C") (class "Default")
      (node (ref "HEADSTAGE") (pin "7") (pinfunction "7_7") (pintype "bidirectional"))
      (node (ref "J6") (pin "3") (pinfunction "3_3") (pintype "passive"))
      (node (ref "R6") (pin "3") (pinfunction "3_3") (pintype "passive"))
      (node (ref "S6") (pin "14") (pinfunction "14_14") (pintype "passive"))
    )
    (net (code "68") (name "TT10D") (class "Default")
      (node (ref "HEADSTAGE") (pin "6") (pinfunction "6_6") (pintype "bidirectional"))
      (node (ref "J6") (pin "4") (pinfunction "4_4") (pintype "passive"))
      (node (ref "R6") (pin "4") (pinfunction "4_4") (pintype "passive"))
      (node (ref "S6") (pin "13") (pinfunction "13_13") (pintype "passive"))
    )
    (net (code "69") (name "TT11A") (class "Default")
      (node (ref "HEADSTAGE") (pin "5") (pinfunction "5_5") (pintype "bidirectional"))
      (node (ref "J6") (pin "5") (pinfunction "5_5") (pintype "passive"))
      (node (ref "R6") (pin "5") (pinfunction "5_5") (pintype "passive"))
      (node (ref "S6") (pin "12") (pinfunction "12_12") (pintype "passive"))
    )
    (net (code "70") (name "TT11B") (class "Default")
      (node (ref "HEADSTAGE") (pin "4") (pinfunction "4_4") (pintype "bidirectional"))
      (node (ref "J6") (pin "6") (pinfunction "6_6") (pintype "passive"))
      (node (ref "R6") (pin "6") (pinfunction "6_6") (pintype "passive"))
      (node (ref "S6") (pin "11") (pinfunction "11_11") (pintype "passive"))
    )
    (net (code "71") (name "TT11C") (class "Default")
      (node (ref "HEADSTAGE") (pin "3") (pinfunction "3_3") (pintype "bidirectional"))
      (node (ref "J6") (pin "7") (pinfunction "7_7") (pintype "passive"))
      (node (ref "R6") (pin "7") (pinfunction "7_7") (pintype "passive"))
      (node (ref "S6") (pin "10") (pinfunction "10_10") (pintype "passive"))
    )
    (net (code "72") (name "TT11D") (class "Default")
      (node (ref "HEADSTAGE") (pin "2") (pinfunction "2_2") (pintype "bidirectional"))
      (node (ref "J6") (pin "8") (pinfunction "8_8") (pintype "passive"))
      (node (ref "R6") (pin "8") (pinfunction "8_8") (pintype "passive"))
      (node (ref "S6") (pin "9") (pinfunction "9_9") (pintype "passive"))
    )
    (net (code "73") (name "TT12A") (class "Default")
      (node (ref "HEADSTAGE") (pin "68") (pinfunction "68_68") (pintype "bidirectional"))
      (node (ref "J7") (pin "1") (pinfunction "1_1") (pintype "passive"))
      (node (ref "R7") (pin "1") (pinfunction "1_1") (pintype "passive"))
      (node (ref "S7") (pin "16") (pinfunction "16_16") (pintype "passive"))
    )
    (net (code "74") (name "TT12B") (class "Default")
      (node (ref "HEADSTAGE") (pin "67") (pinfunction "67_67") (pintype "bidirectional"))
      (node (ref "J7") (pin "2") (pinfunction "2_2") (pintype "passive"))
      (node (ref "R7") (pin "2") (pinfunction "2_2") (pintype "passive"))
      (node (ref "S7") (pin "15") (pinfunction "15_15") (pintype "passive"))
    )
    (net (code "75") (name "TT12C") (class "Default")
      (node (ref "HEADSTAGE") (pin "66") (pinfunction "66_66") (pintype "bidirectional"))
      (node (ref "J7") (pin "3") (pinfunction "3_3") (pintype "passive"))
      (node (ref "R7") (pin "3") (pinfunction "3_3") (pintype "passive"))
      (node (ref "S7") (pin "14") (pinfunction "14_14") (pintype "passive"))
    )
    (net (code "76") (name "TT12D") (class "Default")
      (node (ref "HEADSTAGE") (pin "65") (pinfunction "65_65") (pintype "bidirectional"))
      (node (ref "J7") (pin "4") (pinfunction "4_4") (pintype "passive"))
      (node (ref "R7") (pin "4") (pinfunction "4_4") (pintype "passive"))
      (node (ref "S7") (pin "13") (pinfunction "13_13") (pintype "passive"))
    )
    (net (code "77") (name "TT13A") (class "Default")
      (node (ref "HEADSTAGE") (pin "64") (pinfunction "64_64") (pintype "bidirectional"))
      (node (ref "J7") (pin "5") (pinfunction "5_5") (pintype "passive"))
      (node (ref "R7") (pin "5") (pinfunction "5_5") (pintype "passive"))
      (node (ref "S7") (pin "12") (pinfunction "12_12") (pintype "passive"))
    )
    (net (code "78") (name "TT13B") (class "Default")
      (node (ref "HEADSTAGE") (pin "63") (pinfunction "63_63") (pintype "bidirectional"))
      (node (ref "J7") (pin "6") (pinfunction "6_6") (pintype "passive"))
      (node (ref "R7") (pin "6") (pinfunction "6_6") (pintype "passive"))
      (node (ref "S7") (pin "11") (pinfunction "11_11") (pintype "passive"))
    )
    (net (code "79") (name "TT13C") (class "Default")
      (node (ref "HEADSTAGE") (pin "62") (pinfunction "62_62") (pintype "bidirectional"))
      (node (ref "J7") (pin "7") (pinfunction "7_7") (pintype "passive"))
      (node (ref "R7") (pin "7") (pinfunction "7_7") (pintype "passive"))
      (node (ref "S7") (pin "10") (pinfunction "10_10") (pintype "passive"))
    )
    (net (code "80") (name "TT13D") (class "Default")
      (node (ref "HEADSTAGE") (pin "61") (pinfunction "61_61") (pintype "bidirectional"))
      (node (ref "J7") (pin "8") (pinfunction "8_8") (pintype "passive"))
      (node (ref "R7") (pin "8") (pinfunction "8_8") (pintype "passive"))
      (node (ref "S7") (pin "9") (pinfunction "9_9") (pintype "passive"))
    )
    (net (code "81") (name "TT14A") (class "Default")
      (node (ref "HEADSTAGE") (pin "60") (pinfunction "60_60") (pintype "bidirectional"))
      (node (ref "J8") (pin "1") (pinfunction "1_1") (pintype "passive"))
      (node (ref "R8") (pin "1") (pinfunction "1_1") (pintype "passive"))
      (node (ref "S8") (pin "16") (pinfunction "16_16") (pintype "passive"))
    )
    (net (code "82") (name "TT14B") (class "Default")
      (node (ref "HEADSTAGE") (pin "59") (pinfunction "59_59") (pintype "bidirectional"))
      (node (ref "J8") (pin "2") (pinfunction "2_2") (pintype "passive"))
      (node (ref "R8") (pin "2") (pinfunction "2_2") (pintype "passive"))
      (node (ref "S8") (pin "15") (pinfunction "15_15") (pintype "passive"))
    )
    (net (code "83") (name "TT14C") (class "Default")
      (node (ref "HEADSTAGE") (pin "58") (pinfunction "58_58") (pintype "bidirectional"))
      (node (ref "J8") (pin "3") (pinfunction "3_3") (pintype "passive"))
      (node (ref "R8") (pin "3") (pinfunction "3_3") (pintype "passive"))
      (node (ref "S8") (pin "14") (pinfunction "14_14") (pintype "passive"))
    )
    (net (code "84") (name "TT14D") (class "Default")
      (node (ref "HEADSTAGE") (pin "57") (pinfunction "57_57") (pintype "bidirectional"))
      (node (ref "J8") (pin "4") (pinfunction "4_4") (pintype "passive"))
      (node (ref "R8") (pin "4") (pinfunction "4_4") (pintype "passive"))
      (node (ref "S8") (pin "13") (pinfunction "13_13") (pintype "passive"))
    )
    (net (code "85") (name "TT15A") (class "Default")
      (node (ref "HEADSTAGE") (pin "56") (pinfunction "56_56") (pintype "bidirectional"))
      (node (ref "J8") (pin "5") (pinfunction "5_5") (pintype "passive"))
      (node (ref "R8") (pin "5") (pinfunction "5_5") (pintype "passive"))
      (node (ref "S8") (pin "12") (pinfunction "12_12") (pintype "passive"))
    )
    (net (code "86") (name "TT15B") (class "Default")
      (node (ref "HEADSTAGE") (pin "55") (pinfunction "55_55") (pintype "bidirectional"))
      (node (ref "J8") (pin "6") (pinfunction "6_6") (pintype "passive"))
      (node (ref "R8") (pin "6") (pinfunction "6_6") (pintype "passive"))
      (node (ref "S8") (pin "11") (pinfunction "11_11") (pintype "passive"))
    )
    (net (code "87") (name "TT15C") (class "Default")
      (node (ref "HEADSTAGE") (pin "54") (pinfunction "54_54") (pintype "bidirectional"))
      (node (ref "J8") (pin "7") (pinfunction "7_7") (pintype "passive"))
      (node (ref "R8") (pin "7") (pinfunction "7_7") (pintype "passive"))
      (node (ref "S8") (pin "10") (pinfunction "10_10") (pintype "passive"))
    )
    (net (code "88") (name "TT15D") (class "Default")
      (node (ref "HEADSTAGE") (pin "53") (pinfunction "53_53") (pintype "bidirectional"))
      (node (ref "J8") (pin "8") (pinfunction "8_8") (pintype "passive"))
      (node (ref "R8") (pin "8") (pinfunction "8_8") (pintype "passive"))
      (node (ref "S8") (pin "9") (pinfunction "9_9") (pintype "passive"))
    )
  )
)
